# nixie_test_v3.net
KiCad netlist of a schematic drawn in EAGLE
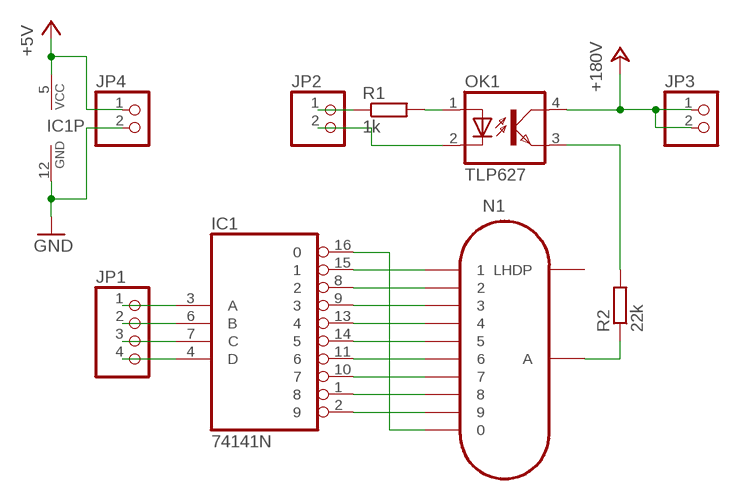
[diagram p0: schematic, sheet 1]

(export (version "E")
  (design (tool "Eeschema 10.0.6"))
  (components
    (comp (ref "IC1")
      (value "74141N")
      (footprint "eagle-import:DIL16")
      (libsource (lib "eagle-import") (part "74141N"))
    )
    (comp (ref "JP1")
      (value "PINHD-1X4")
      (footprint "eagle-import:1X04")
      (libsource (lib "eagle-import") (part "PINHD-1X4"))
    )
    (comp (ref "JP2")
      (value "PINHD-1X2")
      (footprint "eagle-import:1X02")
      (libsource (lib "eagle-import") (part "PINHD-1X2"))
    )
    (comp (ref "JP3")
      (value "PINHD-1X2")
      (footprint "eagle-import:1X02")
      (libsource (lib "eagle-import") (part "PINHD-1X2"))
    )
    (comp (ref "JP4")
      (value "PINHD-1X2")
      (footprint "eagle-import:1X02")
      (libsource (lib "eagle-import") (part "PINHD-1X2"))
    )
    (comp (ref "N1")
      (value "IN-12B")
      (footprint "eagle-import:IN-12")
      (libsource (lib "eagle-import") (part "IN-12B"))
    )
    (comp (ref "OK1")
      (value "TLP627")
      (footprint "eagle-import:4-SMD")
      (libsource (lib "eagle-import") (part "TLP627"))
    )
    (comp (ref "R1")
      (value "1k")
      (footprint "eagle-import:R0805")
      (libsource (lib "eagle-import") (part "R-EU_R0805"))
    )
    (comp (ref "R2")
      (value "22k")
      (footprint "eagle-import:0207_10")
      (libsource (lib "eagle-import") (part "R-EU_10"))
    )
  )
  (nets
    (net (code "1") (name "+5V") (class "Default")
      (node (ref "IC1") (pin "5") (pinfunction "VCC_5") (pintype "power_in"))
      (node (ref "JP4") (pin "1") (pinfunction "1_1") (pintype "passive"))
    )
    (net (code "2") (name "+180V") (class "Default")
      (node (ref "JP3") (pin "1") (pinfunction "1_1") (pintype "passive"))
      (node (ref "JP3") (pin "2") (pinfunction "2_2") (pintype "passive"))
      (node (ref "OK1") (pin "4") (pinfunction "COL_4") (pintype "passive"))
    )
    (net (code "3") (name "GND") (class "Default")
      (node (ref "IC1") (pin "12") (pinfunction "GND_12") (pintype "power_in"))
      (node (ref "JP4") (pin "2") (pinfunction "2_2") (pintype "passive"))
    )
    (net (code "4") (name "Net-(IC1A-0)") (class "Default")
      (node (ref "IC1") (pin "16") (pinfunction "0_16") (pintype "open_collector"))
      (node (ref "N1") (pin "0") (pinfunction "0_0") (pintype "bidirectional"))
    )
    (net (code "5") (name "Net-(IC1A-1)") (class "Default")
      (node (ref "IC1") (pin "15") (pinfunction "1_15") (pintype "open_collector"))
      (node (ref "N1") (pin "1") (pinfunction "1_1") (pintype "bidirectional"))
    )
    (net (code "6") (name "Net-(IC1A-2)") (class "Default")
      (node (ref "IC1") (pin "8") (pinfunction "2_8") (pintype "open_collector"))
      (node (ref "N1") (pin "2") (pinfunction "2_2") (pintype "bidirectional"))
    )
    (net (code "7") (name "Net-(IC1A-3)") (class "Default")
      (node (ref "IC1") (pin "9") (pinfunction "3_9") (pintype "open_collector"))
      (node (ref "N1") (pin "3") (pinfunction "3_3") (pintype "bidirectional"))
    )
    (net (code "8") (name "Net-(IC1A-4)") (class "Default")
      (node (ref "IC1") (pin "13") (pinfunction "4_13") (pintype "open_collector"))
      (node (ref "N1") (pin "4") (pinfunction "4_4") (pintype "bidirectional"))
    )
    (net (code "9") (name "Net-(IC1A-5)") (class "Default")
      (node (ref "IC1") (pin "14") (pinfunction "5_14") (pintype "open_collector"))
      (node (ref "N1") (pin "5") (pinfunction "5_5") (pintype "bidirectional"))
    )
    (net (code "10") (name "Net-(IC1A-6)") (class "Default")
      (node (ref "IC1") (pin "11") (pinfunction "6_11") (pintype "open_collector"))
      (node (ref "N1") (pin "6") (pinfunction "6_6") (pintype "bidirectional"))
    )
    (net (code "11") (name "Net-(IC1A-7)") (class "Default")
      (node (ref "IC1") (pin "10") (pinfunction "7_10") (pintype "open_collector"))
      (node (ref "N1") (pin "7") (pinfunction "7_7") (pintype "bidirectional"))
    )
    (net (code "12") (name "Net-(IC1A-8)") (class "Default")
      (node (ref "IC1") (pin "1") (pinfunction "8_1") (pintype "open_collector"))
      (node (ref "N1") (pin "8") (pinfunction "8_8") (pintype "bidirectional"))
    )
    (net (code "13") (name "Net-(IC1A-9)") (class "Default")
      (node (ref "IC1") (pin "2") (pinfunction "9_2") (pintype "open_collector"))
      (node (ref "N1") (pin "9") (pinfunction "9_9") (pintype "bidirectional"))
    )
    (net (code "14") (name "Net-(IC1A-A)") (class "Default")
      (node (ref "IC1") (pin "3") (pinfunction "A_3") (pintype "input"))
      (node (ref "JP1") (pin "1") (pinfunction "1_1") (pintype "passive"))
    )
    (net (code "15") (name "Net-(IC1A-B)") (class "Default")
      (node (ref "IC1") (pin "6") (pinfunction "B_6") (pintype "input"))
      (node (ref "JP1") (pin "2") (pinfunction "2_2") (pintype "passive"))
    )
    (net (code "16") (name "Net-(IC1A-C)") (class "Default")
      (node (ref "IC1") (pin "7") (pinfunction "C_7") (pintype "input"))
      (node (ref "JP1") (pin "3") (pinfunction "3_3") (pintype "passive"))
    )
    (net (code "17") (name "Net-(IC1A-D)") (class "Default")
      (node (ref "IC1") (pin "4") (pinfunction "D_4") (pintype "input"))
      (node (ref "JP1") (pin "4") (pinfunction "4_4") (pintype "passive"))
    )
    (net (code "18") (name "Net-(JP2-Pad1)") (class "Default")
      (node (ref "JP2") (pin "1") (pinfunction "1_1") (pintype "passive"))
      (node (ref "R1") (pin "1") (pinfunction "1_1") (pintype "passive"))
    )
    (net (code "19") (name "Net-(N1-PadA)") (class "Default")
      (node (ref "N1") (pin "A") (pinfunction "A_A") (pintype "bidirectional"))
      (node (ref "R2") (pin "1") (pinfunction "1_1") (pintype "passive"))
    )
    (net (code "20") (name "Net-(OK1-A)") (class "Default")
      (node (ref "OK1") (pin "1") (pinfunction "A_1") (pintype "passive"))
      (node (ref "R1") (pin "2") (pinfunction "2_2") (pintype "passive"))
    )
    (net (code "21") (name "Net-(OK1-C)") (class "Default")
      (node (ref "JP2") (pin "2") (pinfunction "2_2") (pintype "passive"))
      (node (ref "OK1") (pin "2") (pinfunction "C_2") (pintype "passive"))
    )
    (net (code "22") (name "Net-(OK1-EMIT)") (class "Default")
      (node (ref "OK1") (pin "3") (pinfunction "EMIT_3") (pintype "passive"))
      (node (ref "R2") (pin "2") (pinfunction "2_2") (pintype "passive"))
    )
    (net (code "23") (name "unconnected-(N1-PadLHDP)") (class "Default")
      (node (ref "N1") (pin "LHDP") (pinfunction "LHDP_LHDP") (pintype "bidirectional"))
    )
  )
)
